# EMB1061.net
KiCad netlist of a schematic drawn in EAGLE
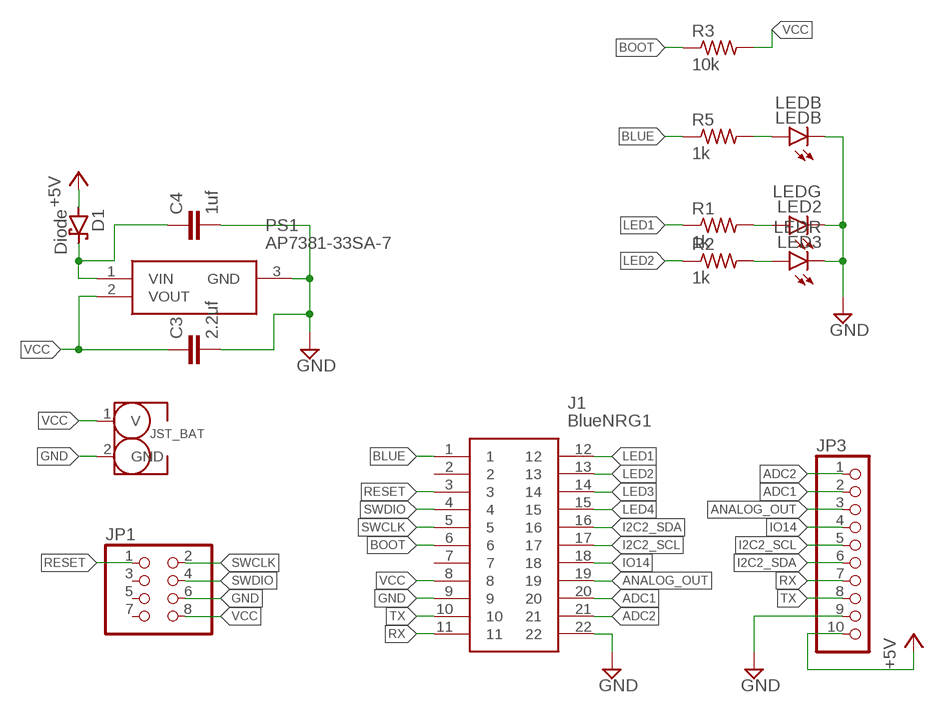
[diagram p0: schematic, sheet 1]

(export (version "E")
  (design (tool "Eeschema 10.0.6"))
  (components
    (comp (ref "C3")
      (value "2.2uf")
      (footprint "eagle-import:C0603K")
      (libsource (lib "eagle-import") (part "C-EUC0603K"))
    )
    (comp (ref "C4")
      (value "1uf")
      (footprint "eagle-import:C0603K")
      (libsource (lib "eagle-import") (part "C-EUC0603K"))
    )
    (comp (ref "D1")
      (value "Diode")
      (footprint "eagle-import:SOD323_ST")
      (libsource (lib "eagle-import") (part "BAT60J"))
    )
    (comp (ref "J1")
      (value "BlueNRG1")
      (footprint "eagle-import:113990637")
      (fields
        (field (name "MANUFACTURER_PART_NUMBER") "113990637")
        (field (name "MOUSER_PART_NUMBER") "713-113990637")
      )
      (libsource (lib "eagle-import") (part "113990637"))
    )
    (comp (ref "JP1")
      (value "PINHD-2X4")
      (footprint "eagle-import:2X04")
      (libsource (lib "eagle-import") (part "PINHD-2X4"))
    )
    (comp (ref "JP3")
      (value "PINHD-1X10")
      (footprint "eagle-import:1X10")
      (libsource (lib "eagle-import") (part "PINHD-1X10"))
    )
    (comp (ref "LED2")
      (value "LEDG")
      (footprint "eagle-import:SML0805")
      (libsource (lib "eagle-import") (part "LEDSML0805"))
    )
    (comp (ref "LED3")
      (value "LEDR")
      (footprint "eagle-import:SML0805")
      (libsource (lib "eagle-import") (part "LEDSML0805"))
    )
    (comp (ref "LEDB")
      (value "LEDB")
      (footprint "eagle-import:SML0805")
      (libsource (lib "eagle-import") (part "LEDSML0805"))
    )
    (comp (ref "PS1")
      (value "AP7381-33SA-7")
      (footprint "eagle-import:SOT96P240X120-3N")
      (fields (field (name "MOUSER_PART_NUMBER") "621-AP7381-33SA-7"))
      (libsource (lib "eagle-import") (part "AP7381-33SA-7"))
    )
    (comp (ref "R1")
      (value "1k")
      (footprint "eagle-import:R0805")
      (libsource (lib "eagle-import") (part "R-US_R0805"))
    )
    (comp (ref "R2")
      (value "1k")
      (footprint "eagle-import:R0805")
      (libsource (lib "eagle-import") (part "R-US_R0805"))
    )
    (comp (ref "R3")
      (value "10k")
      (footprint "eagle-import:R0603")
      (libsource (lib "eagle-import") (part "R-US_R0603"))
    )
    (comp (ref "R5")
      (value "1k")
      (footprint "eagle-import:R0805")
      (libsource (lib "eagle-import") (part "R-US_R0805"))
    )
    (comp (ref "U$1")
      (value "JST2.0MM_2PIN")
      (footprint "eagle-import:JST2.0MM_2PIN")
      (libsource (lib "eagle-import") (part "JST2.0MM_2PIN"))
    )
  )
  (nets
    (net (code "1") (name "+5V") (class "Default")
      (node (ref "D1") (pin "A") (pinfunction "A_A") (pintype "passive"))
      (node (ref "JP3") (pin "10") (pinfunction "10_10") (pintype "passive"))
    )
    (net (code "2") (name "ADC1") (class "Default")
      (node (ref "J1") (pin "20") (pinfunction "20_20") (pintype "bidirectional"))
      (node (ref "JP3") (pin "2") (pinfunction "2_2") (pintype "passive"))
    )
    (net (code "3") (name "ADC2") (class "Default")
      (node (ref "J1") (pin "21") (pinfunction "21_21") (pintype "bidirectional"))
      (node (ref "JP3") (pin "1") (pinfunction "1_1") (pintype "passive"))
    )
    (net (code "4") (name "ANALOG_OUT") (class "Default")
      (node (ref "J1") (pin "19") (pinfunction "19_19") (pintype "bidirectional"))
      (node (ref "JP3") (pin "3") (pinfunction "3_3") (pintype "passive"))
    )
    (net (code "5") (name "BLUE") (class "Default")
      (node (ref "J1") (pin "1") (pinfunction "1_1") (pintype "bidirectional"))
      (node (ref "R5") (pin "1") (pinfunction "1_1") (pintype "passive"))
    )
    (net (code "6") (name "BOOT") (class "Default")
      (node (ref "J1") (pin "6") (pinfunction "6_6") (pintype "bidirectional"))
      (node (ref "R3") (pin "1") (pinfunction "1_1") (pintype "passive"))
    )
    (net (code "7") (name "GND") (class "Default")
      (node (ref "C3") (pin "2") (pinfunction "2_2") (pintype "passive"))
      (node (ref "C4") (pin "2") (pinfunction "2_2") (pintype "passive"))
      (node (ref "J1") (pin "22") (pinfunction "22_22") (pintype "bidirectional"))
      (node (ref "J1") (pin "9") (pinfunction "9_9") (pintype "bidirectional"))
      (node (ref "JP1") (pin "6") (pinfunction "6_6") (pintype "passive"))
      (node (ref "JP3") (pin "9") (pinfunction "9_9") (pintype "passive"))
      (node (ref "LED2") (pin "C") (pinfunction "C_C") (pintype "passive"))
      (node (ref "LED3") (pin "C") (pinfunction "C_C") (pintype "passive"))
      (node (ref "LEDB") (pin "C") (pinfunction "C_C") (pintype "passive"))
      (node (ref "PS1") (pin "3") (pinfunction "GND_3") (pintype "bidirectional"))
      (node (ref "U$1") (pin "2") (pinfunction "GND_2") (pintype "power_in"))
    )
    (net (code "8") (name "I2C2_SCL") (class "Default")
      (node (ref "J1") (pin "17") (pinfunction "17_17") (pintype "bidirectional"))
      (node (ref "JP3") (pin "5") (pinfunction "5_5") (pintype "passive"))
    )
    (net (code "9") (name "I2C2_SDA") (class "Default")
      (node (ref "J1") (pin "16") (pinfunction "16_16") (pintype "bidirectional"))
      (node (ref "JP3") (pin "6") (pinfunction "6_6") (pintype "passive"))
    )
    (net (code "10") (name "IO14") (class "Default")
      (node (ref "J1") (pin "18") (pinfunction "18_18") (pintype "bidirectional"))
      (node (ref "JP3") (pin "4") (pinfunction "4_4") (pintype "passive"))
    )
    (net (code "11") (name "LED1") (class "Default")
      (node (ref "J1") (pin "12") (pinfunction "12_12") (pintype "bidirectional"))
      (node (ref "R1") (pin "1") (pinfunction "1_1") (pintype "passive"))
    )
    (net (code "12") (name "LED2") (class "Default")
      (node (ref "J1") (pin "13") (pinfunction "13_13") (pintype "bidirectional"))
      (node (ref "R2") (pin "1") (pinfunction "1_1") (pintype "passive"))
    )
    (net (code "13") (name "LED3") (class "Default")
      (node (ref "J1") (pin "14") (pinfunction "14_14") (pintype "bidirectional"))
    )
    (net (code "14") (name "LED4") (class "Default")
      (node (ref "J1") (pin "15") (pinfunction "15_15") (pintype "bidirectional"))
    )
    (net (code "15") (name "Net-(LED2-PadA)") (class "Default")
      (node (ref "LED2") (pin "A") (pinfunction "A_A") (pintype "passive"))
      (node (ref "R1") (pin "2") (pinfunction "2_2") (pintype "passive"))
    )
    (net (code "16") (name "Net-(LED3-PadA)") (class "Default")
      (node (ref "LED3") (pin "A") (pinfunction "A_A") (pintype "passive"))
      (node (ref "R2") (pin "2") (pinfunction "2_2") (pintype "passive"))
    )
    (net (code "17") (name "Net-(LEDB-PadA)") (class "Default")
      (node (ref "LEDB") (pin "A") (pinfunction "A_A") (pintype "passive"))
      (node (ref "R5") (pin "2") (pinfunction "2_2") (pintype "passive"))
    )
    (net (code "18") (name "Net-(PS1-VIN)") (class "Default")
      (node (ref "C4") (pin "1") (pinfunction "1_1") (pintype "passive"))
      (node (ref "D1") (pin "C") (pinfunction "C_C") (pintype "passive"))
      (node (ref "PS1") (pin "1") (pinfunction "VIN_1") (pintype "bidirectional"))
    )
    (net (code "19") (name "RESET") (class "Default")
      (node (ref "J1") (pin "3") (pinfunction "3_3") (pintype "bidirectional"))
      (node (ref "JP1") (pin "1") (pinfunction "1_1") (pintype "passive"))
    )
    (net (code "20") (name "RX") (class "Default")
      (node (ref "J1") (pin "11") (pinfunction "11_11") (pintype "bidirectional"))
      (node (ref "JP3") (pin "7") (pinfunction "7_7") (pintype "passive"))
    )
    (net (code "21") (name "SWCLK") (class "Default")
      (node (ref "J1") (pin "5") (pinfunction "5_5") (pintype "bidirectional"))
      (node (ref "JP1") (pin "2") (pinfunction "2_2") (pintype "passive"))
    )
    (net (code "22") (name "SWDIO") (class "Default")
      (node (ref "J1") (pin "4") (pinfunction "4_4") (pintype "bidirectional"))
      (node (ref "JP1") (pin "4") (pinfunction "4_4") (pintype "passive"))
    )
    (net (code "23") (name "TX") (class "Default")
      (node (ref "J1") (pin "10") (pinfunction "10_10") (pintype "bidirectional"))
      (node (ref "JP3") (pin "8") (pinfunction "8_8") (pintype "passive"))
    )
    (net (code "24") (name "VCC") (class "Default")
      (node (ref "C3") (pin "1") (pinfunction "1_1") (pintype "passive"))
      (node (ref "J1") (pin "8") (pinfunction "8_8") (pintype "bidirectional"))
      (node (ref "JP1") (pin "8") (pinfunction "8_8") (pintype "passive"))
      (node (ref "PS1") (pin "2") (pinfunction "VOUT_2") (pintype "bidirectional"))
      (node (ref "R3") (pin "2") (pinfunction "2_2") (pintype "passive"))
      (node (ref "U$1") (pin "1") (pinfunction "V_1") (pintype "power_in"))
    )
    (net (code "25") (name "unconnected-(J1-Pad2)") (class "Default")
      (node (ref "J1") (pin "2") (pinfunction "2_2") (pintype "bidirectional"))
    )
    (net (code "26") (name "unconnected-(J1-Pad7)") (class "Default")
      (node (ref "J1") (pin "7") (pinfunction "7_7") (pintype "bidirectional"))
    )
    (net (code "27") (name "unconnected-(JP1-Pad3)") (class "Default")
      (node (ref "JP1") (pin "3") (pinfunction "3_3") (pintype "passive"))
    )
    (net (code "28") (name "unconnected-(JP1-Pad5)") (class "Default")
      (node (ref "JP1") (pin "5") (pinfunction "5_5") (pintype "passive"))
    )
    (net (code "29") (name "unconnected-(JP1-Pad7)") (class "Default")
      (node (ref "JP1") (pin "7") (pinfunction "7_7") (pintype "passive"))
    )
  )
)
